# sensor_matrix_02.net
KiCad netlist of a schematic drawn in Altium Designer
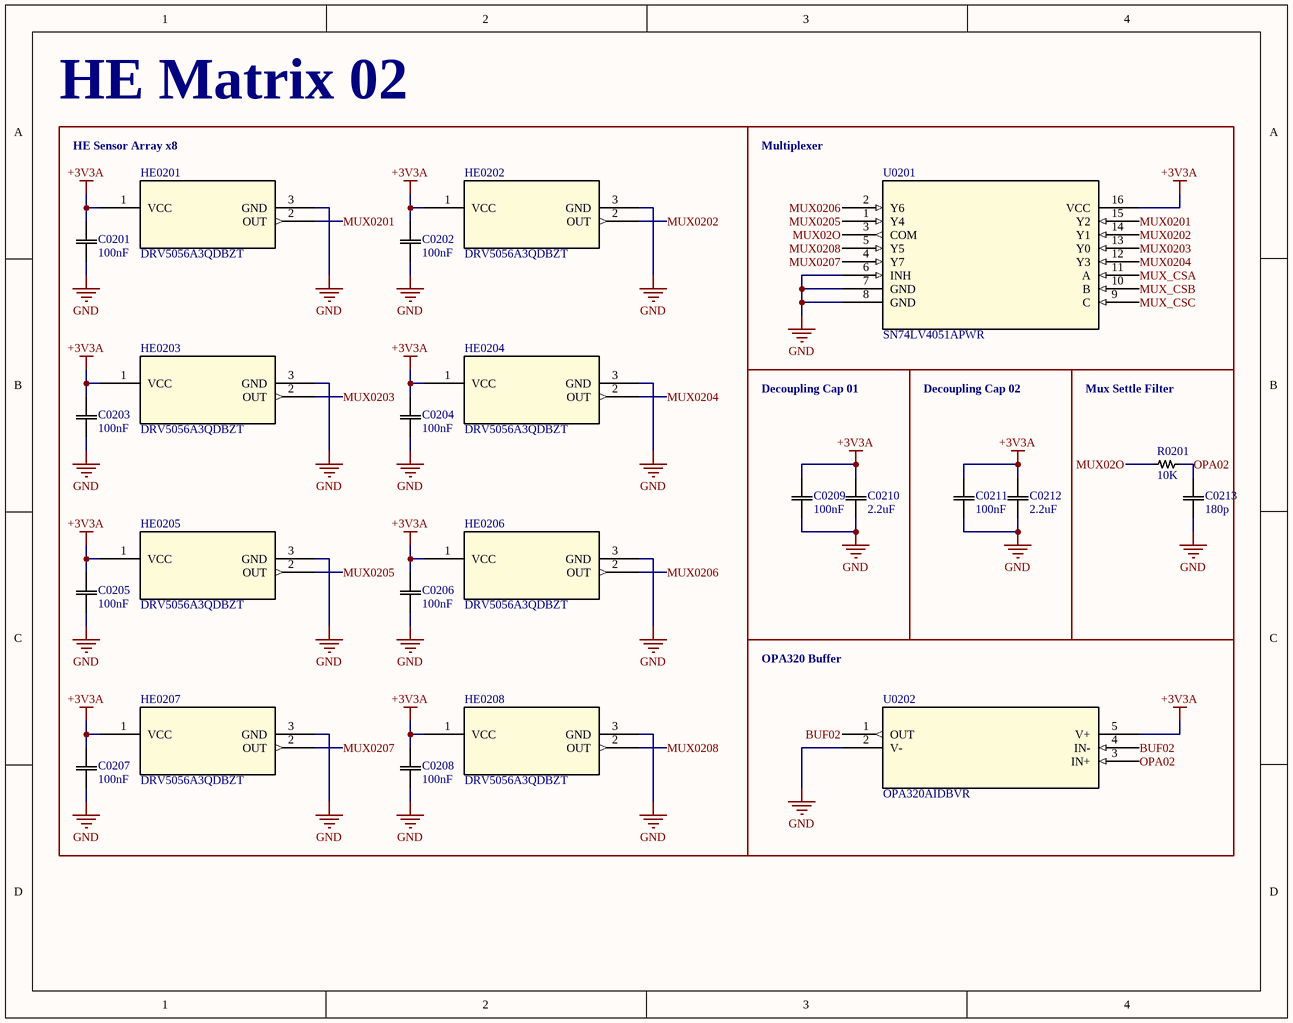
[diagram p0: sensor_matrix_02.SchDoc]

(export (version "E")
  (design (tool "Eeschema 10.0.6"))
  (components
    (comp (ref "C0201")
      (value "100nF")
      (footprint "CAPC10555_55N_KEM")
      (description "SMD Comm X7R, Ceramic, SMD, MLCC, Temperature Stable, 0402")
      (fields
        (field (name "MANUFACTURER_PART_NUMBER") "C0402C104K4RACTU")
        (field (name "COPYRIGHT") "Copyright (C) 2025 Ultra Librarian. All rights reserved.")
      )
      (libsource (lib "SplitHE_Int") (part "C0402"))
    )
    (comp (ref "C0202")
      (value "100nF")
      (footprint "CAPC10555_55N_KEM")
      (description "SMD Comm X7R, Ceramic, SMD, MLCC, Temperature Stable, 0402")
      (fields
        (field (name "MANUFACTURER_PART_NUMBER") "C0402C104K4RACTU")
        (field (name "COPYRIGHT") "Copyright (C) 2025 Ultra Librarian. All rights reserved.")
      )
      (libsource (lib "SplitHE_Int") (part "C0402"))
    )
    (comp (ref "C0203")
      (value "100nF")
      (footprint "CAPC10555_55N_KEM")
      (description "SMD Comm X7R, Ceramic, SMD, MLCC, Temperature Stable, 0402")
      (fields
        (field (name "MANUFACTURER_PART_NUMBER") "C0402C104K4RACTU")
        (field (name "COPYRIGHT") "Copyright (C) 2025 Ultra Librarian. All rights reserved.")
      )
      (libsource (lib "SplitHE_Int") (part "C0402"))
    )
    (comp (ref "C0204")
      (value "100nF")
      (footprint "CAPC10555_55N_KEM")
      (description "SMD Comm X7R, Ceramic, SMD, MLCC, Temperature Stable, 0402")
      (fields
        (field (name "MANUFACTURER_PART_NUMBER") "C0402C104K4RACTU")
        (field (name "COPYRIGHT") "Copyright (C) 2025 Ultra Librarian. All rights reserved.")
      )
      (libsource (lib "SplitHE_Int") (part "C0402"))
    )
    (comp (ref "C0205")
      (value "100nF")
      (footprint "CAPC10555_55N_KEM")
      (description "SMD Comm X7R, Ceramic, SMD, MLCC, Temperature Stable, 0402")
      (fields
        (field (name "MANUFACTURER_PART_NUMBER") "C0402C104K4RACTU")
        (field (name "COPYRIGHT") "Copyright (C) 2025 Ultra Librarian. All rights reserved.")
      )
      (libsource (lib "SplitHE_Int") (part "C0402"))
    )
    (comp (ref "C0206")
      (value "100nF")
      (footprint "CAPC10555_55N_KEM")
      (description "SMD Comm X7R, Ceramic, SMD, MLCC, Temperature Stable, 0402")
      (fields
        (field (name "MANUFACTURER_PART_NUMBER") "C0402C104K4RACTU")
        (field (name "COPYRIGHT") "Copyright (C) 2025 Ultra Librarian. All rights reserved.")
      )
      (libsource (lib "SplitHE_Int") (part "C0402"))
    )
    (comp (ref "C0207")
      (value "100nF")
      (footprint "CAPC10555_55N_KEM")
      (description "SMD Comm X7R, Ceramic, SMD, MLCC, Temperature Stable, 0402")
      (fields
        (field (name "MANUFACTURER_PART_NUMBER") "C0402C104K4RACTU")
        (field (name "COPYRIGHT") "Copyright (C) 2025 Ultra Librarian. All rights reserved.")
      )
      (libsource (lib "SplitHE_Int") (part "C0402"))
    )
    (comp (ref "C0208")
      (value "100nF")
      (footprint "CAPC10555_55N_KEM")
      (description "SMD Comm X7R, Ceramic, SMD, MLCC, Temperature Stable, 0402")
      (fields
        (field (name "MANUFACTURER_PART_NUMBER") "C0402C104K4RACTU")
        (field (name "COPYRIGHT") "Copyright (C) 2025 Ultra Librarian. All rights reserved.")
      )
      (libsource (lib "SplitHE_Int") (part "C0402"))
    )
    (comp (ref "C0209")
      (value "100nF")
      (footprint "CAPC10555_55N_KEM")
      (description "SMD Comm X7R, Ceramic, SMD, MLCC, Temperature Stable, 0402")
      (fields
        (field (name "MANUFACTURER_PART_NUMBER") "C0402C104K4RACTU")
        (field (name "COPYRIGHT") "Copyright (C) 2025 Ultra Librarian. All rights reserved.")
      )
      (libsource (lib "SplitHE_Int") (part "C0402"))
    )
    (comp (ref "C0210")
      (value "2.2uF")
      (footprint "CAPC10555_55N_KEM")
      (description "SMD Comm X7R, Ceramic, SMD, MLCC, Temperature Stable, 0402")
      (fields
        (field (name "MANUFACTURER_PART_NUMBER") "C0402C104K4RACTU")
        (field (name "COPYRIGHT") "Copyright (C) 2025 Ultra Librarian. All rights reserved.")
      )
      (libsource (lib "SplitHE_Int") (part "C0402"))
    )
    (comp (ref "C0211")
      (value "100nF")
      (footprint "CAPC10555_55N_KEM")
      (description "SMD Comm X7R, Ceramic, SMD, MLCC, Temperature Stable, 0402")
      (fields
        (field (name "MANUFACTURER_PART_NUMBER") "C0402C104K4RACTU")
        (field (name "COPYRIGHT") "Copyright (C) 2025 Ultra Librarian. All rights reserved.")
      )
      (libsource (lib "SplitHE_Int") (part "C0402"))
    )
    (comp (ref "C0212")
      (value "2.2uF")
      (footprint "CAPC10555_55N_KEM")
      (description "SMD Comm X7R, Ceramic, SMD, MLCC, Temperature Stable, 0402")
      (fields
        (field (name "MANUFACTURER_PART_NUMBER") "C0402C104K4RACTU")
        (field (name "COPYRIGHT") "Copyright (C) 2025 Ultra Librarian. All rights reserved.")
      )
      (libsource (lib "SplitHE_Int") (part "C0402"))
    )
    (comp (ref "C0213")
      (value "180p")
      (footprint "CAPC10555_55N_KEM")
      (description "SMD Comm X7R, Ceramic, SMD, MLCC, Temperature Stable, 0402")
      (fields
        (field (name "MANUFACTURER_PART_NUMBER") "C0402C104K4RACTU")
        (field (name "COPYRIGHT") "Copyright (C) 2025 Ultra Librarian. All rights reserved.")
      )
      (libsource (lib "SplitHE_Int") (part "C0402"))
    )
    (comp (ref "HE0201")
      (value "DRV5056A3QDBZT")
      (footprint "DBZ3_TEX")
      (description "Ratiometric unipolar linear hall effect sensor with analog output 3-SOT-23 -40 to 125")
      (fields (field (name "COPYRIGHT") "Copyright (C) 2025 Ultra Librarian. All rights reserved."))
      (libsource (lib "DRV5056A3QDBZT") (part "DRV5056A3QDBZT"))
    )
    (comp (ref "HE0202")
      (value "DRV5056A3QDBZT")
      (footprint "DBZ3_TEX")
      (description "Ratiometric unipolar linear hall effect sensor with analog output 3-SOT-23 -40 to 125")
      (fields (field (name "COPYRIGHT") "Copyright (C) 2025 Ultra Librarian. All rights reserved."))
      (libsource (lib "DRV5056A3QDBZT") (part "DRV5056A3QDBZT"))
    )
    (comp (ref "HE0203")
      (value "DRV5056A3QDBZT")
      (footprint "DBZ3_TEX")
      (description "Ratiometric unipolar linear hall effect sensor with analog output 3-SOT-23 -40 to 125")
      (fields (field (name "COPYRIGHT") "Copyright (C) 2025 Ultra Librarian. All rights reserved."))
      (libsource (lib "DRV5056A3QDBZT") (part "DRV5056A3QDBZT"))
    )
    (comp (ref "HE0204")
      (value "DRV5056A3QDBZT")
      (footprint "DBZ3_TEX")
      (description "Ratiometric unipolar linear hall effect sensor with analog output 3-SOT-23 -40 to 125")
      (fields (field (name "COPYRIGHT") "Copyright (C) 2025 Ultra Librarian. All rights reserved."))
      (libsource (lib "DRV5056A3QDBZT") (part "DRV5056A3QDBZT"))
    )
    (comp (ref "HE0205")
      (value "DRV5056A3QDBZT")
      (footprint "DBZ3_TEX")
      (description "Ratiometric unipolar linear hall effect sensor with analog output 3-SOT-23 -40 to 125")
      (fields (field (name "COPYRIGHT") "Copyright (C) 2025 Ultra Librarian. All rights reserved."))
      (libsource (lib "DRV5056A3QDBZT") (part "DRV5056A3QDBZT"))
    )
    (comp (ref "HE0206")
      (value "DRV5056A3QDBZT")
      (footprint "DBZ3_TEX")
      (description "Ratiometric unipolar linear hall effect sensor with analog output 3-SOT-23 -40 to 125")
      (fields (field (name "COPYRIGHT") "Copyright (C) 2025 Ultra Librarian. All rights reserved."))
      (libsource (lib "DRV5056A3QDBZT") (part "DRV5056A3QDBZT"))
    )
    (comp (ref "HE0207")
      (value "DRV5056A3QDBZT")
      (footprint "DBZ3_TEX")
      (description "Ratiometric unipolar linear hall effect sensor with analog output 3-SOT-23 -40 to 125")
      (fields (field (name "COPYRIGHT") "Copyright (C) 2025 Ultra Librarian. All rights reserved."))
      (libsource (lib "DRV5056A3QDBZT") (part "DRV5056A3QDBZT"))
    )
    (comp (ref "HE0208")
      (value "DRV5056A3QDBZT")
      (footprint "DBZ3_TEX")
      (description "Ratiometric unipolar linear hall effect sensor with analog output 3-SOT-23 -40 to 125")
      (fields (field (name "COPYRIGHT") "Copyright (C) 2025 Ultra Librarian. All rights reserved."))
      (libsource (lib "DRV5056A3QDBZT") (part "DRV5056A3QDBZT"))
    )
    (comp (ref "R0201")
      (value "10K")
      (footprint "RES0402_CPF_TYCO_TYC")
      (description "CPF 0402 RL")
      (fields
        (field (name "MANUFACTURER_PART_NUMBER") "CPF0402B33RE1")
        (field (name "COPYRIGHT") "Copyright (C) 2025 Ultra Librarian. All rights reserved.")
      )
      (libsource (lib "SplitHE_Int") (part "R0402"))
    )
    (comp (ref "U0201")
      (value "SN74LV4051APWR")
      (footprint "PW16")
      (description "5V 8:1 one-channel general-purpose analog multiplexer 16-TSSOP -40 to 85")
      (fields (field (name "COPYRIGHT") "Copyright (C) 2025 Ultra Librarian. All rights reserved."))
      (libsource (lib "SN74LV4051APWR") (part "SN74LV4051APWR"))
    )
    (comp (ref "U0202")
      (value "OPA320AIDBVR")
      (footprint "DBV5")
      (description "Precision, zero-crossover, 20-MHz, 0.9-pA Ib, RRIO, CMOS operational amplifier 5-SOT-23 -40 to 125")
      (fields (field (name "COPYRIGHT") "Copyright (C) 2025 Ultra Librarian. All rights reserved."))
      (libsource (lib "OPA320AIDBVR") (part "OPA320AIDBVR"))
    )
  )
  (nets
    (net (code "1") (name "+3V3A") (class "Default")
      (node (ref "C0201") (pin "2") (pinfunction "2_2") (pintype "passive"))
      (node (ref "C0202") (pin "2") (pinfunction "2_2") (pintype "passive"))
      (node (ref "C0203") (pin "2") (pinfunction "2_2") (pintype "passive"))
      (node (ref "C0204") (pin "2") (pinfunction "2_2") (pintype "passive"))
      (node (ref "C0205") (pin "2") (pinfunction "2_2") (pintype "passive"))
      (node (ref "C0206") (pin "2") (pinfunction "2_2") (pintype "passive"))
      (node (ref "C0207") (pin "2") (pinfunction "2_2") (pintype "passive"))
      (node (ref "C0208") (pin "2") (pinfunction "2_2") (pintype "passive"))
      (node (ref "C0209") (pin "2") (pinfunction "2_2") (pintype "passive"))
      (node (ref "C0210") (pin "2") (pinfunction "2_2") (pintype "passive"))
      (node (ref "C0211") (pin "2") (pinfunction "2_2") (pintype "passive"))
      (node (ref "C0212") (pin "2") (pinfunction "2_2") (pintype "passive"))
      (node (ref "HE0201") (pin "1") (pinfunction "VCC_1") (pintype "power_in"))
      (node (ref "HE0202") (pin "1") (pinfunction "VCC_1") (pintype "power_in"))
      (node (ref "HE0203") (pin "1") (pinfunction "VCC_1") (pintype "power_in"))
      (node (ref "HE0204") (pin "1") (pinfunction "VCC_1") (pintype "power_in"))
      (node (ref "HE0205") (pin "1") (pinfunction "VCC_1") (pintype "power_in"))
      (node (ref "HE0206") (pin "1") (pinfunction "VCC_1") (pintype "power_in"))
      (node (ref "HE0207") (pin "1") (pinfunction "VCC_1") (pintype "power_in"))
      (node (ref "HE0208") (pin "1") (pinfunction "VCC_1") (pintype "power_in"))
      (node (ref "U0201") (pin "16") (pinfunction "VCC_16") (pintype "power_in"))
      (node (ref "U0202") (pin "5") (pinfunction "V+_5") (pintype "power_in"))
    )
    (net (code "2") (name "/BUF02") (class "Default")
      (node (ref "U0202") (pin "1") (pinfunction "OUT_1") (pintype "output"))
      (node (ref "U0202") (pin "4") (pinfunction "IN-_4") (pintype "input"))
    )
    (net (code "3") (name "/MUX02O") (class "Default")
      (node (ref "R0201") (pin "2") (pinfunction "2_2") (pintype "passive"))
      (node (ref "U0201") (pin "3") (pinfunction "COM_3") (pintype "output"))
    )
    (net (code "4") (name "/MUX0201") (class "Default")
      (node (ref "HE0201") (pin "2") (pinfunction "OUT_2") (pintype "output"))
      (node (ref "U0201") (pin "15") (pinfunction "Y2_15") (pintype "input"))
    )
    (net (code "5") (name "/MUX0202") (class "Default")
      (node (ref "HE0202") (pin "2") (pinfunction "OUT_2") (pintype "output"))
      (node (ref "U0201") (pin "14") (pinfunction "Y1_14") (pintype "input"))
    )
    (net (code "6") (name "/MUX0203") (class "Default")
      (node (ref "HE0203") (pin "2") (pinfunction "OUT_2") (pintype "output"))
      (node (ref "U0201") (pin "13") (pinfunction "Y0_13") (pintype "input"))
    )
    (net (code "7") (name "/MUX0204") (class "Default")
      (node (ref "HE0204") (pin "2") (pinfunction "OUT_2") (pintype "output"))
      (node (ref "U0201") (pin "12") (pinfunction "Y3_12") (pintype "input"))
    )
    (net (code "8") (name "/MUX0205") (class "Default")
      (node (ref "HE0205") (pin "2") (pinfunction "OUT_2") (pintype "output"))
      (node (ref "U0201") (pin "1") (pinfunction "Y4_1") (pintype "input"))
    )
    (net (code "9") (name "/MUX0206") (class "Default")
      (node (ref "HE0206") (pin "2") (pinfunction "OUT_2") (pintype "output"))
      (node (ref "U0201") (pin "2") (pinfunction "Y6_2") (pintype "input"))
    )
    (net (code "10") (name "/MUX0207") (class "Default")
      (node (ref "HE0207") (pin "2") (pinfunction "OUT_2") (pintype "output"))
      (node (ref "U0201") (pin "4") (pinfunction "Y7_4") (pintype "input"))
    )
    (net (code "11") (name "/MUX0208") (class "Default")
      (node (ref "HE0208") (pin "2") (pinfunction "OUT_2") (pintype "output"))
      (node (ref "U0201") (pin "5") (pinfunction "Y5_5") (pintype "input"))
    )
    (net (code "12") (name "/MUX_CSA") (class "Default")
      (node (ref "U0201") (pin "11") (pinfunction "A_11") (pintype "input"))
    )
    (net (code "13") (name "/MUX_CSB") (class "Default")
      (node (ref "U0201") (pin "10") (pinfunction "B_10") (pintype "input"))
    )
    (net (code "14") (name "/MUX_CSC") (class "Default")
      (node (ref "U0201") (pin "9") (pinfunction "C_9") (pintype "input"))
    )
    (net (code "15") (name "/OPA02") (class "Default")
      (node (ref "C0213") (pin "2") (pinfunction "2_2") (pintype "passive"))
      (node (ref "R0201") (pin "1") (pinfunction "1_1") (pintype "passive"))
      (node (ref "U0202") (pin "3") (pinfunction "IN+_3") (pintype "input"))
    )
    (net (code "16") (name "GND") (class "Default")
      (node (ref "C0201") (pin "1") (pinfunction "1_1") (pintype "passive"))
      (node (ref "C0202") (pin "1") (pinfunction "1_1") (pintype "passive"))
      (node (ref "C0203") (pin "1") (pinfunction "1_1") (pintype "passive"))
      (node (ref "C0204") (pin "1") (pinfunction "1_1") (pintype "passive"))
      (node (ref "C0205") (pin "1") (pinfunction "1_1") (pintype "passive"))
      (node (ref "C0206") (pin "1") (pinfunction "1_1") (pintype "passive"))
      (node (ref "C0207") (pin "1") (pinfunction "1_1") (pintype "passive"))
      (node (ref "C0208") (pin "1") (pinfunction "1_1") (pintype "passive"))
      (node (ref "C0209") (pin "1") (pinfunction "1_1") (pintype "passive"))
      (node (ref "C0210") (pin "1") (pinfunction "1_1") (pintype "passive"))
      (node (ref "C0211") (pin "1") (pinfunction "1_1") (pintype "passive"))
      (node (ref "C0212") (pin "1") (pinfunction "1_1") (pintype "passive"))
      (node (ref "C0213") (pin "1") (pinfunction "1_1") (pintype "passive"))
      (node (ref "HE0201") (pin "3") (pinfunction "GND_3") (pintype "power_in"))
      (node (ref "HE0202") (pin "3") (pinfunction "GND_3") (pintype "power_in"))
      (node (ref "HE0203") (pin "3") (pinfunction "GND_3") (pintype "power_in"))
      (node (ref "HE0204") (pin "3") (pinfunction "GND_3") (pintype "power_in"))
      (node (ref "HE0205") (pin "3") (pinfunction "GND_3") (pintype "power_in"))
      (node (ref "HE0206") (pin "3") (pinfunction "GND_3") (pintype "power_in"))
      (node (ref "HE0207") (pin "3") (pinfunction "GND_3") (pintype "power_in"))
      (node (ref "HE0208") (pin "3") (pinfunction "GND_3") (pintype "power_in"))
      (node (ref "U0201") (pin "6") (pinfunction "INH_6") (pintype "input"))
      (node (ref "U0201") (pin "7") (pinfunction "GND_7") (pintype "power_in"))
      (node (ref "U0201") (pin "8") (pinfunction "GND_8") (pintype "power_in"))
      (node (ref "U0202") (pin "2") (pinfunction "V-_2") (pintype "power_in"))
    )
  )
)
